# midi-vidi.net
KiCad netlist of a schematic drawn in EAGLE
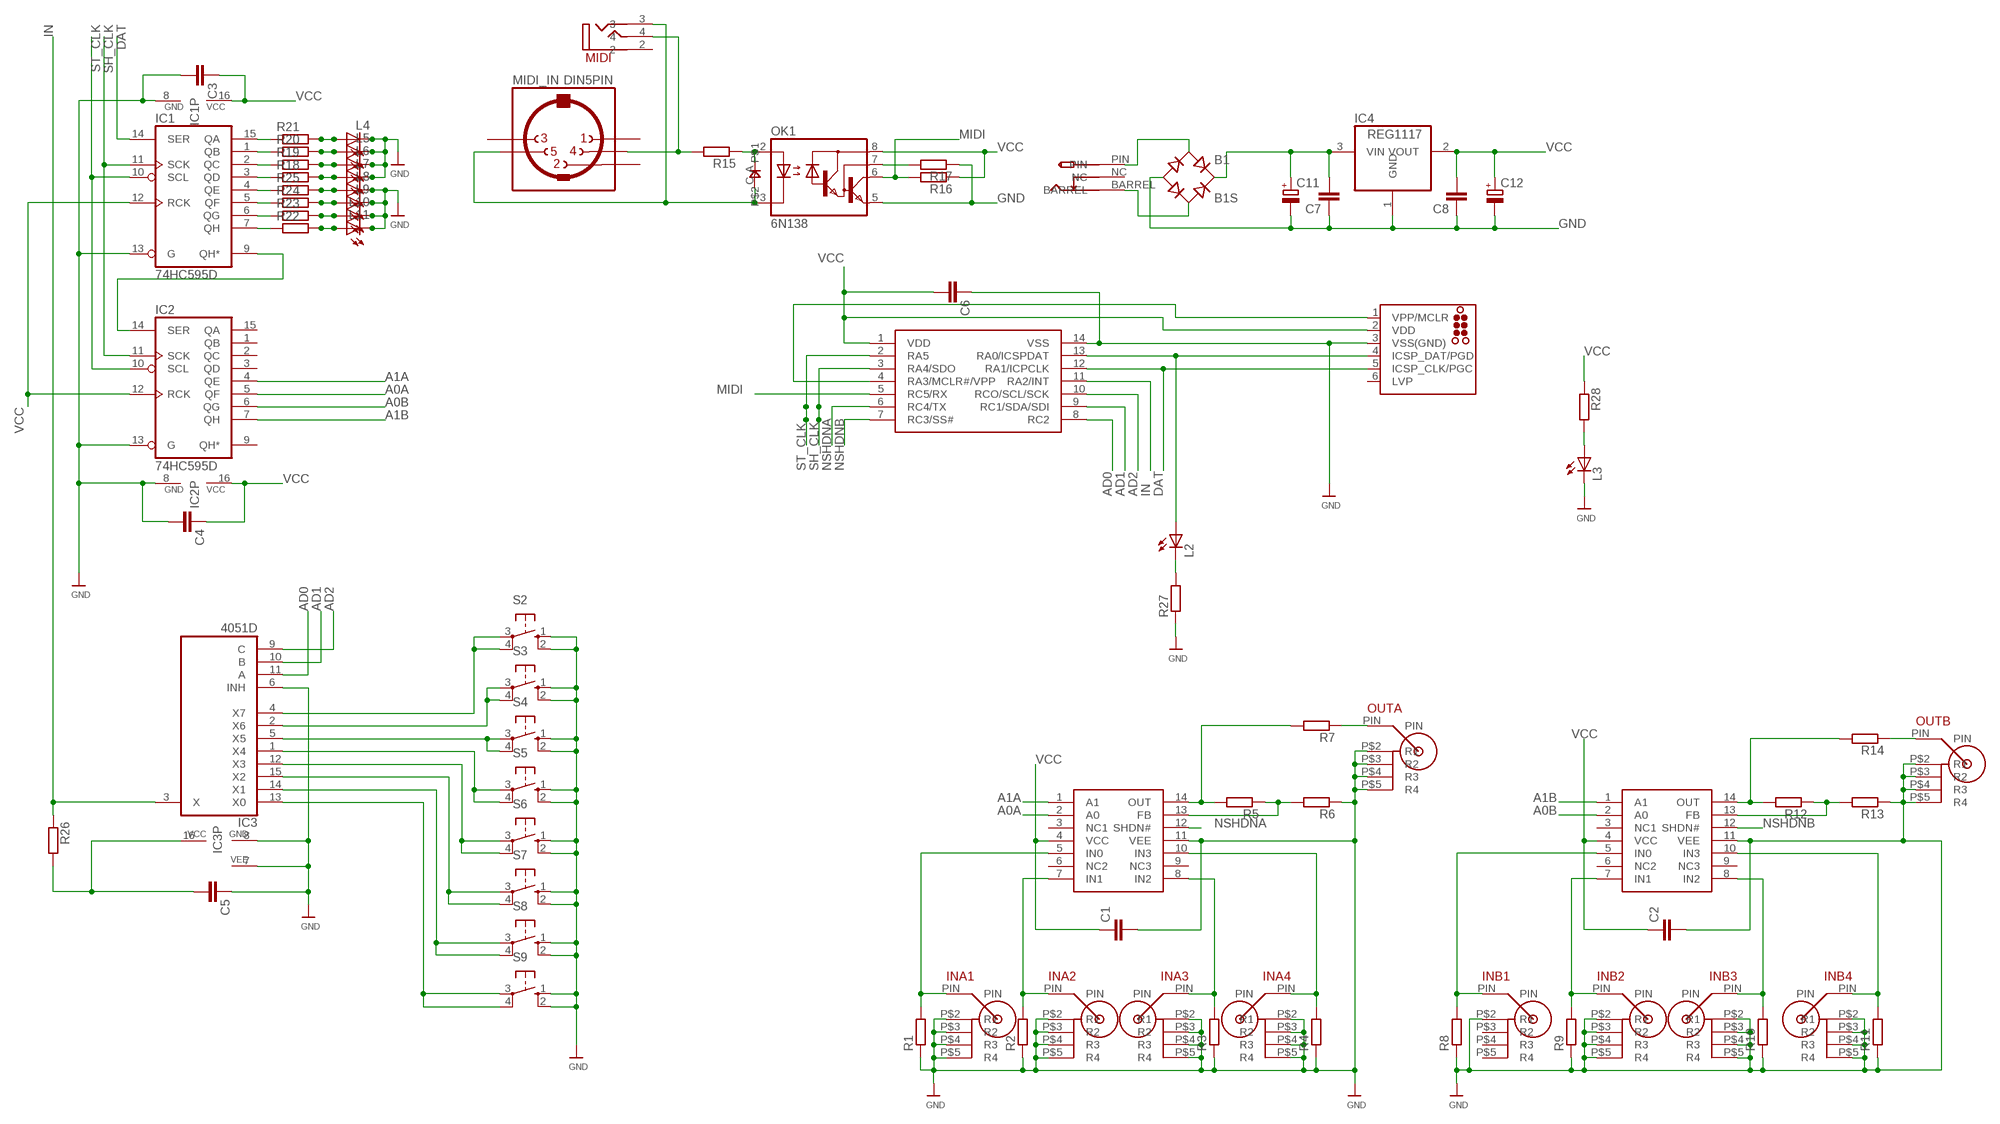
[diagram p0: schematic, sheet 1]

(export (version "E")
  (design (tool "Eeschema 10.0.6"))
  (components
    (comp (ref "B1")
      (value "B1S")
      (footprint "eagle-import:MBS")
      (libsource (lib "eagle-import") (part "BS1"))
    )
    (comp (ref "C1")
      (value "C-EUC0805")
      (footprint "eagle-import:C0805")
      (libsource (lib "eagle-import") (part "C-EUC0805"))
    )
    (comp (ref "C2")
      (value "C-EUC0805")
      (footprint "eagle-import:C0805")
      (libsource (lib "eagle-import") (part "C-EUC0805"))
    )
    (comp (ref "C3")
      (value "C-EUC0805")
      (footprint "eagle-import:C0805")
      (libsource (lib "eagle-import") (part "C-EUC0805"))
    )
    (comp (ref "C4")
      (value "C-EUC0805")
      (footprint "eagle-import:C0805")
      (libsource (lib "eagle-import") (part "C-EUC0805"))
    )
    (comp (ref "C5")
      (value "C-EUC0805")
      (footprint "eagle-import:C0805")
      (libsource (lib "eagle-import") (part "C-EUC0805"))
    )
    (comp (ref "C6")
      (value "C-EUC0805")
      (footprint "eagle-import:C0805")
      (libsource (lib "eagle-import") (part "C-EUC0805"))
    )
    (comp (ref "C7")
      (value "C-EUC0805")
      (footprint "eagle-import:C0805")
      (libsource (lib "eagle-import") (part "C-EUC0805"))
    )
    (comp (ref "C8")
      (value "C-EUC0805")
      (footprint "eagle-import:C0805")
      (libsource (lib "eagle-import") (part "C-EUC0805"))
    )
    (comp (ref "C11")
      (value "CPOL-EUE2,5-6E")
      (footprint "eagle-import:E2,5-6E")
      (libsource (lib "eagle-import") (part "CPOL-EUE2,5-6E"))
    )
    (comp (ref "C12")
      (value "CPOL-EUE2,5-6E")
      (footprint "eagle-import:E2,5-6E")
      (libsource (lib "eagle-import") (part "CPOL-EUE2,5-6E"))
    )
    (comp (ref "IC1")
      (value "74HC595D")
      (footprint "eagle-import:SO16")
      (libsource (lib "eagle-import") (part "74595DHC"))
    )
    (comp (ref "IC2")
      (value "74HC595D")
      (footprint "eagle-import:SO16")
      (libsource (lib "eagle-import") (part "74595DHC"))
    )
    (comp (ref "IC3")
      (value "4051D")
      (footprint "eagle-import:SO16")
      (libsource (lib "eagle-import") (part "4051D"))
    )
    (comp (ref "IC4")
      (value "REG1117")
      (footprint "eagle-import:SOT223")
      (libsource (lib "eagle-import") (part "REG1117"))
    )
    (comp (ref "INA1")
      (value "RCAVERT")
      (footprint "eagle-import:RCAVERT")
      (libsource (lib "eagle-import") (part "RCAVERT"))
    )
    (comp (ref "INA2")
      (value "RCAVERT")
      (footprint "eagle-import:RCAVERT")
      (libsource (lib "eagle-import") (part "RCAVERT"))
    )
    (comp (ref "INA3")
      (value "RCAVERT")
      (footprint "eagle-import:RCAVERT")
      (libsource (lib "eagle-import") (part "RCAVERT"))
    )
    (comp (ref "INA4")
      (value "RCAVERT")
      (footprint "eagle-import:RCAVERT")
      (libsource (lib "eagle-import") (part "RCAVERT"))
    )
    (comp (ref "INB1")
      (value "RCAVERT")
      (footprint "eagle-import:RCAVERT")
      (libsource (lib "eagle-import") (part "RCAVERT"))
    )
    (comp (ref "INB2")
      (value "RCAVERT")
      (footprint "eagle-import:RCAVERT")
      (libsource (lib "eagle-import") (part "RCAVERT"))
    )
    (comp (ref "INB3")
      (value "RCAVERT")
      (footprint "eagle-import:RCAVERT")
      (libsource (lib "eagle-import") (part "RCAVERT"))
    )
    (comp (ref "INB4")
      (value "RCAVERT")
      (footprint "eagle-import:RCAVERT")
      (libsource (lib "eagle-import") (part "RCAVERT"))
    )
    (comp (ref "J1")
      (value "TC2030-MCP-NL")
      (footprint "eagle-import:TC2030-MCP-NL")
      (libsource (lib "eagle-import") (part "TC2030-MCP-NL"))
    )
    (comp (ref "L2")
      (value "LED3MM")
      (footprint "eagle-import:LED3MM")
      (libsource (lib "eagle-import") (part "LED3MM"))
    )
    (comp (ref "L3")
      (value "LED3MM")
      (footprint "eagle-import:LED3MM")
      (libsource (lib "eagle-import") (part "LED3MM"))
    )
    (comp (ref "L4")
      (value "LED3MM")
      (footprint "eagle-import:LED3MM")
      (libsource (lib "eagle-import") (part "LED3MM"))
    )
    (comp (ref "L5")
      (value "LED3MM")
      (footprint "eagle-import:LED3MM")
      (libsource (lib "eagle-import") (part "LED3MM"))
    )
    (comp (ref "L6")
      (value "LED3MM")
      (footprint "eagle-import:LED3MM")
      (libsource (lib "eagle-import") (part "LED3MM"))
    )
    (comp (ref "L7")
      (value "LED3MM")
      (footprint "eagle-import:LED3MM")
      (libsource (lib "eagle-import") (part "LED3MM"))
    )
    (comp (ref "L8")
      (value "LED3MM")
      (footprint "eagle-import:LED3MM")
      (libsource (lib "eagle-import") (part "LED3MM"))
    )
    (comp (ref "L9")
      (value "LED3MM")
      (footprint "eagle-import:LED3MM")
      (libsource (lib "eagle-import") (part "LED3MM"))
    )
    (comp (ref "L10")
      (value "LED3MM")
      (footprint "eagle-import:LED3MM")
      (libsource (lib "eagle-import") (part "LED3MM"))
    )
    (comp (ref "L11")
      (value "LED3MM")
      (footprint "eagle-import:LED3MM")
      (libsource (lib "eagle-import") (part "LED3MM"))
    )
    (comp (ref "MIDI")
      (value "VERTICAL_3_5MM_SOCKET")
      (footprint "eagle-import:VERTICAL_3_5MM_SOCKET")
      (libsource (lib "eagle-import") (part "VERTICAL_3_5MM_SOCKET"))
    )
    (comp (ref "MIDI_IN")
      (value "DIN5PIN")
      (footprint "eagle-import:EDGEDIN")
      (libsource (lib "eagle-import") (part "DIN5PIN"))
    )
    (comp (ref "OK1")
      (value "6N138")
      (footprint "eagle-import:DIL08")
      (fields (field (name "MF") "VISHAY/TELEFUNKEN"))
      (libsource (lib "eagle-import") (part "6N138"))
    )
    (comp (ref "OUTA")
      (value "RCAVERT")
      (footprint "eagle-import:RCAVERT")
      (libsource (lib "eagle-import") (part "RCAVERT"))
    )
    (comp (ref "OUTB")
      (value "RCAVERT")
      (footprint "eagle-import:RCAVERT")
      (libsource (lib "eagle-import") (part "RCAVERT"))
    )
    (comp (ref "R1")
      (value "R-EU_R0805")
      (footprint "eagle-import:R0805")
      (libsource (lib "eagle-import") (part "R-EU_R0805"))
    )
    (comp (ref "R2")
      (value "R-EU_R0805")
      (footprint "eagle-import:R0805")
      (libsource (lib "eagle-import") (part "R-EU_R0805"))
    )
    (comp (ref "R3")
      (value "R-EU_R0805")
      (footprint "eagle-import:R0805")
      (libsource (lib "eagle-import") (part "R-EU_R0805"))
    )
    (comp (ref "R4")
      (value "R-EU_R0805")
      (footprint "eagle-import:R0805")
      (libsource (lib "eagle-import") (part "R-EU_R0805"))
    )
    (comp (ref "R5")
      (value "R-EU_R0805")
      (footprint "eagle-import:R0805")
      (libsource (lib "eagle-import") (part "R-EU_R0805"))
    )
    (comp (ref "R6")
      (value "R-EU_R0805")
      (footprint "eagle-import:R0805")
      (libsource (lib "eagle-import") (part "R-EU_R0805"))
    )
    (comp (ref "R7")
      (value "R-EU_R0805")
      (footprint "eagle-import:R0805")
      (libsource (lib "eagle-import") (part "R-EU_R0805"))
    )
    (comp (ref "R8")
      (value "R-EU_R0805")
      (footprint "eagle-import:R0805")
      (libsource (lib "eagle-import") (part "R-EU_R0805"))
    )
    (comp (ref "R9")
      (value "R-EU_R0805")
      (footprint "eagle-import:R0805")
      (libsource (lib "eagle-import") (part "R-EU_R0805"))
    )
    (comp (ref "R10")
      (value "R-EU_R0805")
      (footprint "eagle-import:R0805")
      (libsource (lib "eagle-import") (part "R-EU_R0805"))
    )
    (comp (ref "R11")
      (value "R-EU_R0805")
      (footprint "eagle-import:R0805")
      (libsource (lib "eagle-import") (part "R-EU_R0805"))
    )
    (comp (ref "R12")
      (value "R-EU_R0805")
      (footprint "eagle-import:R0805")
      (libsource (lib "eagle-import") (part "R-EU_R0805"))
    )
    (comp (ref "R13")
      (value "R-EU_R0805")
      (footprint "eagle-import:R0805")
      (libsource (lib "eagle-import") (part "R-EU_R0805"))
    )
    (comp (ref "R14")
      (value "R-EU_R0805")
      (footprint "eagle-import:R0805")
      (libsource (lib "eagle-import") (part "R-EU_R0805"))
    )
    (comp (ref "R15")
      (value "R-EU_R0805")
      (footprint "eagle-import:R0805")
      (libsource (lib "eagle-import") (part "R-EU_R0805"))
    )
    (comp (ref "R16")
      (value "R-EU_R0805")
      (footprint "eagle-import:R0805")
      (libsource (lib "eagle-import") (part "R-EU_R0805"))
    )
    (comp (ref "R17")
      (value "R-EU_R0805")
      (footprint "eagle-import:R0805")
      (libsource (lib "eagle-import") (part "R-EU_R0805"))
    )
    (comp (ref "R18")
      (value "R-EU_R0805")
      (footprint "eagle-import:R0805")
      (libsource (lib "eagle-import") (part "R-EU_R0805"))
    )
    (comp (ref "R19")
      (value "R-EU_R0805")
      (footprint "eagle-import:R0805")
      (libsource (lib "eagle-import") (part "R-EU_R0805"))
    )
    (comp (ref "R20")
      (value "R-EU_R0805")
      (footprint "eagle-import:R0805")
      (libsource (lib "eagle-import") (part "R-EU_R0805"))
    )
    (comp (ref "R21")
      (value "R-EU_R0805")
      (footprint "eagle-import:R0805")
      (libsource (lib "eagle-import") (part "R-EU_R0805"))
    )
    (comp (ref "R22")
      (value "R-EU_R0805")
      (footprint "eagle-import:R0805")
      (libsource (lib "eagle-import") (part "R-EU_R0805"))
    )
    (comp (ref "R23")
      (value "R-EU_R0805")
      (footprint "eagle-import:R0805")
      (libsource (lib "eagle-import") (part "R-EU_R0805"))
    )
    (comp (ref "R24")
      (value "R-EU_R0805")
      (footprint "eagle-import:R0805")
      (libsource (lib "eagle-import") (part "R-EU_R0805"))
    )
    (comp (ref "R25")
      (value "R-EU_R0805")
      (footprint "eagle-import:R0805")
      (libsource (lib "eagle-import") (part "R-EU_R0805"))
    )
    (comp (ref "R26")
      (value "R-EU_R0805")
      (footprint "eagle-import:R0805")
      (libsource (lib "eagle-import") (part "R-EU_R0805"))
    )
    (comp (ref "R27")
      (value "R-EU_R0805")
      (footprint "eagle-import:R0805")
      (libsource (lib "eagle-import") (part "R-EU_R0805"))
    )
    (comp (ref "R28")
      (value "R-EU_R0805")
      (footprint "eagle-import:R0805")
      (libsource (lib "eagle-import") (part "R-EU_R0805"))
    )
    (comp (ref "S2")
      (value "10-XX")
      (footprint "eagle-import:B3F-10XX")
      (fields (field (name "MPN") "B3F-1000"))
      (libsource (lib "eagle-import") (part "10-XX"))
    )
    (comp (ref "S3")
      (value "10-XX")
      (footprint "eagle-import:B3F-10XX")
      (fields (field (name "MPN") "B3F-1000"))
      (libsource (lib "eagle-import") (part "10-XX"))
    )
    (comp (ref "S4")
      (value "10-XX")
      (footprint "eagle-import:B3F-10XX")
      (fields (field (name "MPN") "B3F-1000"))
      (libsource (lib "eagle-import") (part "10-XX"))
    )
    (comp (ref "S5")
      (value "10-XX")
      (footprint "eagle-import:B3F-10XX")
      (fields (field (name "MPN") "B3F-1000"))
      (libsource (lib "eagle-import") (part "10-XX"))
    )
    (comp (ref "S6")
      (value "10-XX")
      (footprint "eagle-import:B3F-10XX")
      (fields (field (name "MPN") "B3F-1000"))
      (libsource (lib "eagle-import") (part "10-XX"))
    )
    (comp (ref "S7")
      (value "10-XX")
      (footprint "eagle-import:B3F-10XX")
      (fields (field (name "MPN") "B3F-1000"))
      (libsource (lib "eagle-import") (part "10-XX"))
    )
    (comp (ref "S8")
      (value "10-XX")
      (footprint "eagle-import:B3F-10XX")
      (fields (field (name "MPN") "B3F-1000"))
      (libsource (lib "eagle-import") (part "10-XX"))
    )
    (comp (ref "S9")
      (value "10-XX")
      (footprint "eagle-import:B3F-10XX")
      (fields (field (name "MPN") "B3F-1000"))
      (libsource (lib "eagle-import") (part "10-XX"))
    )
    (comp (ref "U$2")
      (value "PWR_SOCKET_2_1MM")
      (footprint "eagle-import:PWR_SOCKET_2_1MM")
      (libsource (lib "eagle-import") (part "PWR_SOCKET_2_1MM"))
    )
    (comp (ref "U$5")
      (value "0805DIODE")
      (footprint "eagle-import:0805DIODE")
      (libsource (lib "eagle-import") (part "0805DIODE"))
    )
    (comp (ref "U$12")
      (value "MAX4311SO14")
      (footprint "eagle-import:SO14")
      (libsource (lib "eagle-import") (part "MAX4311SO14"))
    )
    (comp (ref "U$13")
      (value "MAX4311SO14")
      (footprint "eagle-import:SO14")
      (libsource (lib "eagle-import") (part "MAX4311SO14"))
    )
    (comp (ref "U$14")
      (value "PIC16F1825SO14")
      (footprint "eagle-import:SO14")
      (libsource (lib "eagle-import") (part "PIC16F1825SO14"))
    )
  )
  (nets
    (net (code "1") (name "/A0A") (class "Default")
      (node (ref "IC2") (pin "5") (pinfunction "QF_5") (pintype "tri_state"))
      (node (ref "U$13") (pin "2") (pinfunction "A0_2") (pintype "bidirectional"))
    )
    (net (code "2") (name "/A0B") (class "Default")
      (node (ref "IC2") (pin "6") (pinfunction "QG_6") (pintype "tri_state"))
      (node (ref "U$12") (pin "2") (pinfunction "A0_2") (pintype "bidirectional"))
    )
    (net (code "3") (name "/A1A") (class "Default")
      (node (ref "IC2") (pin "4") (pinfunction "QE_4") (pintype "tri_state"))
      (node (ref "U$13") (pin "1") (pinfunction "A1_1") (pintype "bidirectional"))
    )
    (net (code "4") (name "/A1B") (class "Default")
      (node (ref "IC2") (pin "7") (pinfunction "QH_7") (pintype "tri_state"))
      (node (ref "U$12") (pin "1") (pinfunction "A1_1") (pintype "bidirectional"))
    )
    (net (code "5") (name "/AD0") (class "Default")
      (node (ref "IC3") (pin "11") (pinfunction "A_11") (pintype "input"))
      (node (ref "U$14") (pin "8") (pinfunction "RC2_8") (pintype "bidirectional"))
    )
    (net (code "6") (name "/AD1") (class "Default")
      (node (ref "IC3") (pin "10") (pinfunction "B_10") (pintype "input"))
      (node (ref "U$14") (pin "9") (pinfunction "RC1/SDA/SDI_9") (pintype "bidirectional"))
    )
    (net (code "7") (name "/AD2") (class "Default")
      (node (ref "IC3") (pin "9") (pinfunction "C_9") (pintype "input"))
      (node (ref "U$14") (pin "10") (pinfunction "RCO/SCL/SCK_10") (pintype "bidirectional"))
    )
    (net (code "8") (name "/DAT") (class "Default")
      (node (ref "IC1") (pin "14") (pinfunction "SER_14") (pintype "input"))
      (node (ref "J1") (pin "5") (pinfunction "ICSP_CLK/PGC_5") (pintype "output"))
      (node (ref "U$14") (pin "12") (pinfunction "RA1/ICPCLK_12") (pintype "bidirectional"))
    )
    (net (code "9") (name "/IN") (class "Default")
      (node (ref "IC3") (pin "3") (pinfunction "X_3") (pintype "bidirectional"))
      (node (ref "R26") (pin "1") (pinfunction "1_1") (pintype "passive"))
      (node (ref "U$14") (pin "11") (pinfunction "RA2/INT_11") (pintype "bidirectional"))
    )
    (net (code "10") (name "/MIDI") (class "Default")
      (node (ref "OK1") (pin "6") (pinfunction "VO_6") (pintype "passive"))
      (node (ref "R16") (pin "2") (pinfunction "2_2") (pintype "passive"))
      (node (ref "U$14") (pin "5") (pinfunction "RC5/RX_5") (pintype "bidirectional"))
    )
    (net (code "11") (name "/NSHDNA") (class "Default")
      (node (ref "U$13") (pin "12") (pinfunction "SHDN#_12") (pintype "bidirectional"))
      (node (ref "U$14") (pin "6") (pinfunction "RC4/TX_6") (pintype "bidirectional"))
    )
    (net (code "12") (name "/NSHDNB") (class "Default")
      (node (ref "U$12") (pin "12") (pinfunction "SHDN#_12") (pintype "bidirectional"))
      (node (ref "U$14") (pin "7") (pinfunction "RC3/SS#_7") (pintype "bidirectional"))
    )
    (net (code "13") (name "/SH_CLK") (class "Default")
      (node (ref "IC1") (pin "11") (pinfunction "SCK_11") (pintype "input"))
      (node (ref "IC2") (pin "11") (pinfunction "SCK_11") (pintype "input"))
      (node (ref "U$14") (pin "3") (pinfunction "RA4/SDO_3") (pintype "bidirectional"))
    )
    (net (code "14") (name "/ST_CLK") (class "Default")
      (node (ref "IC1") (pin "10") (pinfunction "SCL_10") (pintype "input"))
      (node (ref "IC2") (pin "10") (pinfunction "SCL_10") (pintype "input"))
      (node (ref "U$14") (pin "2") (pinfunction "RA5_2") (pintype "bidirectional"))
    )
    (net (code "15") (name "/VCC") (class "Default")
      (node (ref "C1") (pin "1") (pinfunction "1_1") (pintype "passive"))
      (node (ref "C12") (pin "+") (pinfunction "+_+") (pintype "passive"))
      (node (ref "C2") (pin "1") (pinfunction "1_1") (pintype "passive"))
      (node (ref "C3") (pin "1") (pinfunction "1_1") (pintype "passive"))
      (node (ref "C4") (pin "1") (pinfunction "1_1") (pintype "passive"))
      (node (ref "C5") (pin "2") (pinfunction "2_2") (pintype "passive"))
      (node (ref "C6") (pin "2") (pinfunction "2_2") (pintype "passive"))
      (node (ref "C8") (pin "2") (pinfunction "2_2") (pintype "passive"))
      (node (ref "IC1") (pin "12") (pinfunction "RCK_12") (pintype "input"))
      (node (ref "IC1") (pin "16") (pinfunction "VCC_16") (pintype "power_in"))
      (node (ref "IC2") (pin "12") (pinfunction "RCK_12") (pintype "input"))
      (node (ref "IC2") (pin "16") (pinfunction "VCC_16") (pintype "power_in"))
      (node (ref "IC3") (pin "16") (pinfunction "VCC_16") (pintype "power_in"))
      (node (ref "IC4") (pin "2") (pinfunction "VOUT_2") (pintype "output"))
      (node (ref "J1") (pin "2") (pinfunction "VDD_2") (pintype "power_in"))
      (node (ref "OK1") (pin "8") (pinfunction "VCC_8") (pintype "passive"))
      (node (ref "R16") (pin "1") (pinfunction "1_1") (pintype "passive"))
      (node (ref "R26") (pin "2") (pinfunction "2_2") (pintype "passive"))
      (node (ref "R28") (pin "1") (pinfunction "1_1") (pintype "passive"))
      (node (ref "U$12") (pin "4") (pinfunction "VCC_4") (pintype "bidirectional"))
      (node (ref "U$13") (pin "4") (pinfunction "VCC_4") (pintype "bidirectional"))
      (node (ref "U$14") (pin "1") (pinfunction "VDD_1") (pintype "power_in"))
    )
    (net (code "16") (name "GND") (class "Default")
      (node (ref "B1") (pin "-") (pinfunction "-_-") (pintype "passive"))
      (node (ref "C1") (pin "2") (pinfunction "2_2") (pintype "passive"))
      (node (ref "C11") (pin "-") (pinfunction "-_-") (pintype "passive"))
      (node (ref "C12") (pin "-") (pinfunction "-_-") (pintype "passive"))
      (node (ref "C2") (pin "2") (pinfunction "2_2") (pintype "passive"))
      (node (ref "C3") (pin "2") (pinfunction "2_2") (pintype "passive"))
      (node (ref "C4") (pin "2") (pinfunction "2_2") (pintype "passive"))
      (node (ref "C5") (pin "1") (pinfunction "1_1") (pintype "passive"))
      (node (ref "C6") (pin "1") (pinfunction "1_1") (pintype "passive"))
      (node (ref "C7") (pin "1") (pinfunction "1_1") (pintype "passive"))
      (node (ref "C8") (pin "1") (pinfunction "1_1") (pintype "passive"))
      (node (ref "IC1") (pin "13") (pinfunction "G_13") (pintype "input"))
      (node (ref "IC1") (pin "8") (pinfunction "GND_8") (pintype "power_in"))
      (node (ref "IC2") (pin "13") (pinfunction "G_13") (pintype "input"))
      (node (ref "IC2") (pin "8") (pinfunction "GND_8") (pintype "power_in"))
      (node (ref "IC3") (pin "6") (pinfunction "INH_6") (pintype "input"))
      (node (ref "IC3") (pin "7") (pinfunction "VEE_7") (pintype "power_in"))
      (node (ref "IC3") (pin "8") (pinfunction "GND_8") (pintype "power_in"))
      (node (ref "IC4") (pin "1") (pinfunction "GND_1") (pintype "power_in"))
      (node (ref "INA1") (pin "P$2") (pinfunction "R1_P$2") (pintype "bidirectional"))
      (node (ref "INA1") (pin "P$3") (pinfunction "R2_P$3") (pintype "bidirectional"))
      (node (ref "INA1") (pin "P$4") (pinfunction "R3_P$4") (pintype "bidirectional"))
      (node (ref "INA1") (pin "P$5") (pinfunction "R4_P$5") (pintype "bidirectional"))
      (node (ref "INA2") (pin "P$2") (pinfunction "R1_P$2") (pintype "bidirectional"))
      (node (ref "INA2") (pin "P$3") (pinfunction "R2_P$3") (pintype "bidirectional"))
      (node (ref "INA2") (pin "P$4") (pinfunction "R3_P$4") (pintype "bidirectional"))
      (node (ref "INA2") (pin "P$5") (pinfunction "R4_P$5") (pintype "bidirectional"))
      (node (ref "INA3") (pin "P$2") (pinfunction "R1_P$2") (pintype "bidirectional"))
      (node (ref "INA3") (pin "P$3") (pinfunction "R2_P$3") (pintype "bidirectional"))
      (node (ref "INA3") (pin "P$4") (pinfunction "R3_P$4") (pintype "bidirectional"))
      (node (ref "INA3") (pin "P$5") (pinfunction "R4_P$5") (pintype "bidirectional"))
      (node (ref "INA4") (pin "P$2") (pinfunction "R1_P$2") (pintype "bidirectional"))
      (node (ref "INA4") (pin "P$3") (pinfunction "R2_P$3") (pintype "bidirectional"))
      (node (ref "INA4") (pin "P$4") (pinfunction "R3_P$4") (pintype "bidirectional"))
      (node (ref "INA4") (pin "P$5") (pinfunction "R4_P$5") (pintype "bidirectional"))
      (node (ref "INB1") (pin "P$2") (pinfunction "R1_P$2") (pintype "bidirectional"))
      (node (ref "INB2") (pin "P$2") (pinfunction "R1_P$2") (pintype "bidirectional"))
      (node (ref "INB2") (pin "P$3") (pinfunction "R2_P$3") (pintype "bidirectional"))
      (node (ref "INB2") (pin "P$4") (pinfunction "R3_P$4") (pintype "bidirectional"))
      (node (ref "INB2") (pin "P$5") (pinfunction "R4_P$5") (pintype "bidirectional"))
      (node (ref "INB3") (pin "P$2") (pinfunction "R1_P$2") (pintype "bidirectional"))
      (node (ref "INB3") (pin "P$3") (pinfunction "R2_P$3") (pintype "bidirectional"))
      (node (ref "INB3") (pin "P$4") (pinfunction "R3_P$4") (pintype "bidirectional"))
      (node (ref "INB3") (pin "P$5") (pinfunction "R4_P$5") (pintype "bidirectional"))
      (node (ref "INB4") (pin "P$2") (pinfunction "R1_P$2") (pintype "bidirectional"))
      (node (ref "INB4") (pin "P$3") (pinfunction "R2_P$3") (pintype "bidirectional"))
      (node (ref "INB4") (pin "P$4") (pinfunction "R3_P$4") (pintype "bidirectional"))
      (node (ref "INB4") (pin "P$5") (pinfunction "R4_P$5") (pintype "bidirectional"))
      (node (ref "J1") (pin "3") (pinfunction "VSS(GND)_3") (pintype "power_in"))
      (node (ref "L10") (pin "K") (pinfunction "C_K") (pintype "passive"))
      (node (ref "L11") (pin "K") (pinfunction "C_K") (pintype "passive"))
      (node (ref "L3") (pin "K") (pinfunction "C_K") (pintype "passive"))
      (node (ref "L4") (pin "K") (pinfunction "C_K") (pintype "passive"))
      (node (ref "L5") (pin "K") (pinfunction "C_K") (pintype "passive"))
      (node (ref "L6") (pin "K") (pinfunction "C_K") (pintype "passive"))
      (node (ref "L7") (pin "K") (pinfunction "C_K") (pintype "passive"))
      (node (ref "L8") (pin "K") (pinfunction "C_K") (pintype "passive"))
      (node (ref "L9") (pin "K") (pinfunction "C_K") (pintype "passive"))
      (node (ref "OK1") (pin "5") (pinfunction "GND_5") (pintype "passive"))
      (node (ref "OUTA") (pin "P$2") (pinfunction "R1_P$2") (pintype "bidirectional"))
      (node (ref "OUTA") (pin "P$3") (pinfunction "R2_P$3") (pintype "bidirectional"))
      (node (ref "OUTA") (pin "P$4") (pinfunction "R3_P$4") (pintype "bidirectional"))
      (node (ref "OUTA") (pin "P$5") (pinfunction "R4_P$5") (pintype "bidirectional"))
      (node (ref "OUTB") (pin "P$2") (pinfunction "R1_P$2") (pintype "bidirectional"))
      (node (ref "OUTB") (pin "P$3") (pinfunction "R2_P$3") (pintype "bidirectional"))
      (node (ref "OUTB") (pin "P$4") (pinfunction "R3_P$4") (pintype "bidirectional"))
      (node (ref "OUTB") (pin "P$5") (pinfunction "R4_P$5") (pintype "bidirectional"))
      (node (ref "R1") (pin "1") (pinfunction "1_1") (pintype "passive"))
      (node (ref "R10") (pin "1") (pinfunction "1_1") (pintype "passive"))
      (node (ref "R11") (pin "1") (pinfunction "1_1") (pintype "passive"))
      (node (ref "R13") (pin "1") (pinfunction "1_1") (pintype "passive"))
      (node (ref "R17") (pin "1") (pinfunction "1_1") (pintype "passive"))
      (node (ref "R2") (pin "1") (pinfunction "1_1") (pintype "passive"))
      (node (ref "R27") (pin "1") (pinfunction "1_1") (pintype "passive"))
      (node (ref "R3") (pin "1") (pinfunction "1_1") (pintype "passive"))
      (node (ref "R4") (pin "1") (pinfunction "1_1") (pintype "passive"))
      (node (ref "R6") (pin "1") (pinfunction "1_1") (pintype "passive"))
      (node (ref "R8") (pin "1") (pinfunction "1_1") (pintype "passive"))
      (node (ref "R9") (pin "1") (pinfunction "1_1") (pintype "passive"))
      (node (ref "S2") (pin "1") (pinfunction "S_1") (pintype "passive"))
      (node (ref "S2") (pin "2") (pinfunction "S1_2") (pintype "passive"))
      (node (ref "S3") (pin "1") (pinfunction "S_1") (pintype "passive"))
      (node (ref "S3") (pin "2") (pinfunction "S1_2") (pintype "passive"))
      (node (ref "S4") (pin "1") (pinfunction "S_1") (pintype "passive"))
      (node (ref "S4") (pin "2") (pinfunction "S1_2") (pintype "passive"))
      (node (ref "S5") (pin "1") (pinfunction "S_1") (pintype "passive"))
      (node (ref "S5") (pin "2") (pinfunction "S1_2") (pintype "passive"))
      (node (ref "S6") (pin "1") (pinfunction "S_1") (pintype "passive"))
      (node (ref "S6") (pin "2") (pinfunction "S1_2") (pintype "passive"))
      (node (ref "S7") (pin "1") (pinfunction "S_1") (pintype "passive"))
      (node (ref "S7") (pin "2") (pinfunction "S1_2") (pintype "passive"))
      (node (ref "S8") (pin "1") (pinfunction "S_1") (pintype "passive"))
      (node (ref "S8") (pin "2") (pinfunction "S1_2") (pintype "passive"))
      (node (ref "S9") (pin "1") (pinfunction "S_1") (pintype "passive"))
      (node (ref "S9") (pin "2") (pinfunction "S1_2") (pintype "passive"))
      (node (ref "U$12") (pin "11") (pinfunction "VEE_11") (pintype "bidirectional"))
      (node (ref "U$13") (pin "11") (pinfunction "VEE_11") (pintype "bidirectional"))
      (node (ref "U$14") (pin "14") (pinfunction "VSS_14") (pintype "power_in"))
    )
    (net (code "17") (name "Net-(B1-PadAC1)") (class "Default")
      (node (ref "B1") (pin "AC1") (pinfunction "AC1_AC1") (pintype "passive"))
      (node (ref "U$2") (pin "PIN") (pinfunction "PIN_PIN") (pintype "bidirectional"))
    )
    (net (code "18") (name "Net-(B1-PadAC2)") (class "Default")
      (node (ref "B1") (pin "AC2") (pinfunction "AC2_AC2") (pintype "passive"))
      (node (ref "U$2") (pin "BARREL") (pinfunction "BARREL_BARREL") (pintype "bidirectional"))
    )
    (net (code "19") (name "Net-(IC1A-QA)") (class "Default")
      (node (ref "IC1") (pin "15") (pinfunction "QA_15") (pintype "tri_state"))
      (node (ref "R21") (pin "1") (pinfunction "1_1") (pintype "passive"))
    )
    (net (code "20") (name "Net-(IC1A-QB)") (class "Default")
      (node (ref "IC1") (pin "1") (pinfunction "QB_1") (pintype "tri_state"))
      (node (ref "R20") (pin "1") (pinfunction "1_1") (pintype "passive"))
    )
    (net (code "21") (name "Net-(IC1A-QC)") (class "Default")
      (node (ref "IC1") (pin "2") (pinfunction "QC_2") (pintype "tri_state"))
      (node (ref "R19") (pin "1") (pinfunction "1_1") (pintype "passive"))
    )
    (net (code "22") (name "Net-(IC1A-QD)") (class "Default")
      (node (ref "IC1") (pin "3") (pinfunction "QD_3") (pintype "tri_state"))
      (node (ref "R18") (pin "1") (pinfunction "1_1") (pintype "passive"))
    )
    (net (code "23") (name "Net-(IC1A-QE)") (class "Default")
      (node (ref "IC1") (pin "4") (pinfunction "QE_4") (pintype "tri_state"))
      (node (ref "R25") (pin "1") (pinfunction "1_1") (pintype "passive"))
    )
    (net (code "24") (name "Net-(IC1A-QF)") (class "Default")
      (node (ref "IC1") (pin "5") (pinfunction "QF_5") (pintype "tri_state"))
      (node (ref "R24") (pin "1") (pinfunction "1_1") (pintype "passive"))
    )
    (net (code "25") (name "Net-(IC1A-QG)") (class "Default")
      (node (ref "IC1") (pin "6") (pinfunction "QG_6") (pintype "tri_state"))
      (node (ref "R23") (pin "1") (pinfunction "1_1") (pintype "passive"))
    )
    (net (code "26") (name "Net-(IC1A-QH)") (class "Default")
      (node (ref "IC1") (pin "7") (pinfunction "QH_7") (pintype "tri_state"))
      (node (ref "R22") (pin "1") (pinfunction "1_1") (pintype "passive"))
    )
    (net (code "27") (name "Net-(IC1A-QH*)") (class "Default")
      (node (ref "IC1") (pin "9") (pinfunction "QH*_9") (pintype "tri_state"))
      (node (ref "IC2") (pin "14") (pinfunction "SER_14") (pintype "input"))
    )
    (net (code "28") (name "Net-(IC3A-X0)") (class "Default")
      (node (ref "IC3") (pin "13") (pinfunction "X0_13") (pintype "bidirectional"))
      (node (ref "S9") (pin "3") (pinfunction "P_3") (pintype "passive"))
      (node (ref "S9") (pin "4") (pinfunction "P1_4") (pintype "passive"))
    )
    (net (code "29") (name "Net-(IC3A-X1)") (class "Default")
      (node (ref "IC3") (pin "14") (pinfunction "X1_14") (pintype "bidirectional"))
      (node (ref "S8") (pin "3") (pinfunction "P_3") (pintype "passive"))
      (node (ref "S8") (pin "4") (pinfunction "P1_4") (pintype "passive"))
    )
    (net (code "30") (name "Net-(IC3A-X2)") (class "Default")
      (node (ref "IC3") (pin "15") (pinfunction "X2_15") (pintype "bidirectional"))
      (node (ref "S7") (pin "3") (pinfunction "P_3") (pintype "passive"))
      (node (ref "S7") (pin "4") (pinfunction "P1_4") (pintype "passive"))
    )
    (net (code "31") (name "Net-(IC3A-X3)") (class "Default")
      (node (ref "IC3") (pin "12") (pinfunction "X3_12") (pintype "bidirectional"))
      (node (ref "S6") (pin "3") (pinfunction "P_3") (pintype "passive"))
      (node (ref "S6") (pin "4") (pinfunction "P1_4") (pintype "passive"))
    )
    (net (code "32") (name "Net-(IC3A-X4)") (class "Default")
      (node (ref "IC3") (pin "1") (pinfunction "X4_1") (pintype "bidirectional"))
      (node (ref "S5") (pin "3") (pinfunction "P_3") (pintype "passive"))
      (node (ref "S5") (pin "4") (pinfunction "P1_4") (pintype "passive"))
    )
    (net (code "33") (name "Net-(IC3A-X5)") (class "Default")
      (node (ref "IC3") (pin "5") (pinfunction "X5_5") (pintype "bidirectional"))
      (node (ref "S4") (pin "3") (pinfunction "P_3") (pintype "passive"))
      (node (ref "S4") (pin "4") (pinfunction "P1_4") (pintype "passive"))
    )
    (net (code "34") (name "Net-(IC3A-X6)") (class "Default")
      (node (ref "IC3") (pin "2") (pinfunction "X6_2") (pintype "bidirectional"))
      (node (ref "S3") (pin "3") (pinfunction "P_3") (pintype "passive"))
      (node (ref "S3") (pin "4") (pinfunction "P1_4") (pintype "passive"))
    )
    (net (code "35") (name "Net-(IC3A-X7)") (class "Default")
      (node (ref "IC3") (pin "4") (pinfunction "X7_4") (pintype "bidirectional"))
      (node (ref "S2") (pin "3") (pinfunction "P_3") (pintype "passive"))
      (node (ref "S2") (pin "4") (pinfunction "P1_4") (pintype "passive"))
    )
    (net (code "36") (name "Net-(IC4-VIN)") (class "Default")
      (node (ref "B1") (pin "+") (pinfunction "+_+") (pintype "passive"))
      (node (ref "C11") (pin "+") (pinfunction "+_+") (pintype "passive"))
      (node (ref "C7") (pin "2") (pinfunction "2_2") (pintype "passive"))
      (node (ref "IC4") (pin "3") (pinfunction "VIN_3") (pintype "input"))
    )
    (net (code "37") (name "Net-(J1-ICSP_DAT{slash}PGD)") (class "Default")
      (node (ref "J1") (pin "4") (pinfunction "ICSP_DAT/PGD_4") (pintype "bidirectional"))
      (node (ref "L2") (pin "A") (pinfunction "A_A") (pintype "passive"))
      (node (ref "U$14") (pin "13") (pinfunction "RA0/ICSPDAT_13") (pintype "bidirectional"))
    )
    (net (code "38") (name "Net-(J1-VPP{slash}MCLR)") (class "Default")
      (node (ref "J1") (pin "1") (pinfunction "VPP/MCLR_1") (pintype "passive"))
      (node (ref "U$14") (pin "4") (pinfunction "RA3/MCLR#/VPP_4") (pintype "input"))
    )
    (net (code "39") (name "Net-(L2-C)") (class "Default")
      (node (ref "L2") (pin "K") (pinfunction "C_K") (pintype "passive"))
      (node (ref "R27") (pin "2") (pinfunction "2_2") (pintype "passive"))
    )
    (net (code "40") (name "Net-(L3-PadA)") (class "Default")
      (node (ref "L3") (pin "A") (pinfunction "A_A") (pintype "passive"))
      (node (ref "R28") (pin "2") (pinfunction "2_2") (pintype "passive"))
    )
    (net (code "41") (name "Net-(L4-PadA)") (class "Default")
      (node (ref "L4") (pin "A") (pinfunction "A_A") (pintype "passive"))
      (node (ref "R21") (pin "2") (pinfunction "2_2") (pintype "passive"))
    )
    (net (code "42") (name "Net-(L5-PadA)") (class "Default")
      (node (ref "L5") (pin "A") (pinfunction "A_A") (pintype "passive"))
      (node (ref "R20") (pin "2") (pinfunction "2_2") (pintype "passive"))
    )
    (net (code "43") (name "Net-(L6-PadA)") (class "Default")
      (node (ref "L6") (pin "A") (pinfunction "A_A") (pintype "passive"))
      (node (ref "R19") (pin "2") (pinfunction "2_2") (pintype "passive"))
    )
    (net (code "44") (name "Net-(L7-PadA)") (class "Default")
      (node (ref "L7") (pin "A") (pinfunction "A_A") (pintype "passive"))
      (node (ref "R18") (pin "2") (pinfunction "2_2") (pintype "passive"))
    )
    (net (code "45") (name "Net-(L8-PadA)") (class "Default")
      (node (ref "L8") (pin "A") (pinfunction "A_A") (pintype "passive"))
      (node (ref "R25") (pin "2") (pinfunction "2_2") (pintype "passive"))
    )
    (net (code "46") (name "Net-(L9-PadA)") (class "Default")
      (node (ref "L9") (pin "A") (pinfunction "A_A") (pintype "passive"))
      (node (ref "R24") (pin "2") (pinfunction "2_2") (pintype "passive"))
    )
    (net (code "47") (name "Net-(L10-PadA)") (class "Default")
      (node (ref "L10") (pin "A") (pinfunction "A_A") (pintype "passive"))
      (node (ref "R23") (pin "2") (pinfunction "2_2") (pintype "passive"))
    )
    (net (code "48") (name "Net-(L11-PadA)") (class "Default")
      (node (ref "L11") (pin "A") (pinfunction "A_A") (pintype "passive"))
      (node (ref "R22") (pin "2") (pinfunction "2_2") (pintype "passive"))
    )
    (net (code "49") (name "Net-(MIDI-Pad4)") (class "Default")
      (node (ref "MIDI") (pin "4") (pinfunction "4_4") (pintype "bidirectional"))
      (node (ref "MIDI_IN") (pin "4") (pinfunction "4_4") (pintype "passive"))
      (node (ref "R15") (pin "2") (pinfunction "2_2") (pintype "passive"))
    )
    (net (code "50") (name "Net-(OK1-A)") (class "Default")
      (node (ref "OK1") (pin "2") (pinfunction "A_2") (pintype "passive"))
      (node (ref "R15") (pin "1") (pinfunction "1_1") (pintype "passive"))
      (node (ref "U$5") (pin "A") (pinfunction "P$2_A") (pintype "bidirectional"))
    )
    (net (code "51") (name "Net-(OK1-C)") (class "Default")
      (node (ref "MIDI") (pin "3") (pinfunction "3_3") (pintype "bidirectional"))
      (node (ref "MIDI_IN") (pin "5") (pinfunction "5_5") (pintype "passive"))
      (node (ref "OK1") (pin "3") (pinfunction "C_3") (pintype "passive"))
      (node (ref "U$5") (pin "C") (pinfunction "P$1_C") (pintype "bidirectional"))
    )
    (net (code "52") (name "Net-(OK1-VB)") (class "Default")
      (node (ref "OK1") (pin "7") (pinfunction "VB_7") (pintype "passive"))
      (node (ref "R17") (pin "2") (pinfunction "2_2") (pintype "passive"))
    )
    (net (code "53") (name "Net-(OUTA-PadPIN)") (class "Default")
      (node (ref "OUTA") (pin "PIN") (pinfunction "PIN_PIN") (pintype "bidirectional"))
      (node (ref "R7") (pin "1") (pinfunction "1_1") (pintype "passive"))
    )
    (net (code "54") (name "Net-(OUTB-PadPIN)") (class "Default")
      (node (ref "OUTB") (pin "PIN") (pinfunction "PIN_PIN") (pintype "bidirectional"))
      (node (ref "R14") (pin "1") (pinfunction "1_1") (pintype "passive"))
    )
    (net (code "55") (name "Net-(U$12-FB)") (class "Default")
      (node (ref "R12") (pin "1") (pinfunction "1_1") (pintype "passive"))
      (node (ref "R13") (pin "2") (pinfunction "2_2") (pintype "passive"))
      (node (ref "U$12") (pin "13") (pinfunction "FB_13") (pintype "bidirectional"))
    )
    (net (code "56") (name "Net-(U$12-IN0)") (class "Default")
      (node (ref "INB1") (pin "PIN") (pinfunction "PIN_PIN") (pintype "bidirectional"))
      (node (ref "R8") (pin "2") (pinfunction "2_2") (pintype "passive"))
      (node (ref "U$12") (pin "5") (pinfunction "IN0_5") (pintype "bidirectional"))
    )
    (net (code "57") (name "Net-(U$12-IN1)") (class "Default")
      (node (ref "INB2") (pin "PIN") (pinfunction "PIN_PIN") (pintype "bidirectional"))
      (node (ref "R9") (pin "2") (pinfunction "2_2") (pintype "passive"))
      (node (ref "U$12") (pin "7") (pinfunction "IN1_7") (pintype "bidirectional"))
    )
    (net (code "58") (name "Net-(U$12-IN2)") (class "Default")
      (node (ref "INB3") (pin "PIN") (pinfunction "PIN_PIN") (pintype "bidirectional"))
      (node (ref "R10") (pin "2") (pinfunction "2_2") (pintype "passive"))
      (node (ref "U$12") (pin "8") (pinfunction "IN2_8") (pintype "bidirectional"))
    )
    (net (code "59") (name "Net-(U$12-IN3)") (class "Default")
      (node (ref "INB4") (pin "PIN") (pinfunction "PIN_PIN") (pintype "bidirectional"))
      (node (ref "R11") (pin "2") (pinfunction "2_2") (pintype "passive"))
      (node (ref "U$12") (pin "10") (pinfunction "IN3_10") (pintype "bidirectional"))
    )
    (net (code "60") (name "Net-(U$12-OUT)") (class "Default")
      (node (ref "R12") (pin "2") (pinfunction "2_2") (pintype "passive"))
      (node (ref "R14") (pin "2") (pinfunction "2_2") (pintype "passive"))
      (node (ref "U$12") (pin "14") (pinfunction "OUT_14") (pintype "bidirectional"))
    )
    (net (code "61") (name "Net-(U$13-FB)") (class "Default")
      (node (ref "R5") (pin "1") (pinfunction "1_1") (pintype "passive"))
      (node (ref "R6") (pin "2") (pinfunction "2_2") (pintype "passive"))
      (node (ref "U$13") (pin "13") (pinfunction "FB_13") (pintype "bidirectional"))
    )
    (net (code "62") (name "Net-(U$13-IN0)") (class "Default")
      (node (ref "INA1") (pin "PIN") (pinfunction "PIN_PIN") (pintype "bidirectional"))
      (node (ref "R1") (pin "2") (pinfunction "2_2") (pintype "passive"))
      (node (ref "U$13") (pin "5") (pinfunction "IN0_5") (pintype "bidirectional"))
    )
    (net (code "63") (name "Net-(U$13-IN1)") (class "Default")
      (node (ref "INA2") (pin "PIN") (pinfunction "PIN_PIN") (pintype "bidirectional"))
      (node (ref "R2") (pin "2") (pinfunction "2_2") (pintype "passive"))
      (node (ref "U$13") (pin "7") (pinfunction "IN1_7") (pintype "bidirectional"))
    )
    (net (code "64") (name "Net-(U$13-IN2)") (class "Default")
      (node (ref "INA3") (pin "PIN") (pinfunction "PIN_PIN") (pintype "bidirectional"))
      (node (ref "R3") (pin "2") (pinfunction "2_2") (pintype "passive"))
      (node (ref "U$13") (pin "8") (pinfunction "IN2_8") (pintype "bidirectional"))
    )
    (net (code "65") (name "Net-(U$13-IN3)") (class "Default")
      (node (ref "INA4") (pin "PIN") (pinfunction "PIN_PIN") (pintype "bidirectional"))
      (node (ref "R4") (pin "2") (pinfunction "2_2") (pintype "passive"))
      (node (ref "U$13") (pin "10") (pinfunction "IN3_10") (pintype "bidirectional"))
    )
    (net (code "66") (name "Net-(U$13-OUT)") (class "Default")
      (node (ref "R5") (pin "2") (pinfunction "2_2") (pintype "passive"))
      (node (ref "R7") (pin "2") (pinfunction "2_2") (pintype "passive"))
      (node (ref "U$13") (pin "14") (pinfunction "OUT_14") (pintype "bidirectional"))
    )
    (net (code "67") (name "unconnected-(IC2A-QA-Pad15)") (class "Default")
      (node (ref "IC2") (pin "15") (pinfunction "QA_15") (pintype "tri_state"))
    )
    (net (code "68") (name "unconnected-(IC2A-QB-Pad1)") (class "Default")
      (node (ref "IC2") (pin "1") (pinfunction "QB_1") (pintype "tri_state"))
    )
    (net (code "69") (name "unconnected-(IC2A-QC-Pad2)") (class "Default")
      (node (ref "IC2") (pin "2") (pinfunction "QC_2") (pintype "tri_state"))
    )
    (net (code "70") (name "unconnected-(IC2A-QD-Pad3)") (class "Default")
      (node (ref "IC2") (pin "3") (pinfunction "QD_3") (pintype "tri_state"))
    )
    (net (code "71") (name "unconnected-(IC2A-QH*-Pad9)") (class "Default")
      (node (ref "IC2") (pin "9") (pinfunction "QH*_9") (pintype "tri_state"))
    )
    (net (code "72") (name "unconnected-(INB1-R2-PadP$3)") (class "Default")
      (node (ref "INB1") (pin "P$3") (pinfunction "R2_P$3") (pintype "bidirectional"))
    )
    (net (code "73") (name "unconnected-(INB1-R3-PadP$4)") (class "Default")
      (node (ref "INB1") (pin "P$4") (pinfunction "R3_P$4") (pintype "bidirectional"))
    )
    (net (code "74") (name "unconnected-(INB1-R4-PadP$5)") (class "Default")
      (node (ref "INB1") (pin "P$5") (pinfunction "R4_P$5") (pintype "bidirectional"))
    )
    (net (code "75") (name "unconnected-(J1-LVP-Pad6)") (class "Default")
      (node (ref "J1") (pin "6") (pinfunction "LVP_6") (pintype "bidirectional"))
    )
    (net (code "76") (name "unconnected-(MIDI-Pad2)") (class "Default")
      (node (ref "MIDI") (pin "2") (pinfunction "2_2") (pintype "bidirectional"))
    )
    (net (code "77") (name "unconnected-(MIDI_IN-Pad1)") (class "Default")
      (node (ref "MIDI_IN") (pin "1") (pinfunction "1_1") (pintype "passive"))
    )
    (net (code "78") (name "unconnected-(MIDI_IN-Pad2)") (class "Default")
      (node (ref "MIDI_IN") (pin "2") (pinfunction "2_2") (pintype "passive"))
    )
    (net (code "79") (name "unconnected-(MIDI_IN-Pad3)") (class "Default")
      (node (ref "MIDI_IN") (pin "3") (pinfunction "3_3") (pintype "passive"))
    )
    (net (code "80") (name "unconnected-(U$2-PadNC)") (class "Default")
      (node (ref "U$2") (pin "NC") (pinfunction "NC_NC") (pintype "bidirectional"))
    )
    (net (code "81") (name "unconnected-(U$12-NC1-Pad3)") (class "Default")
      (node (ref "U$12") (pin "3") (pinfunction "NC1_3") (pintype "bidirectional"))
    )
    (net (code "82") (name "unconnected-(U$12-NC2-Pad6)") (class "Default")
      (node (ref "U$12") (pin "6") (pinfunction "NC2_6") (pintype "bidirectional"))
    )
    (net (code "83") (name "unconnected-(U$12-NC3-Pad9)") (class "Default")
      (node (ref "U$12") (pin "9") (pinfunction "NC3_9") (pintype "bidirectional"))
    )
    (net (code "84") (name "unconnected-(U$13-NC1-Pad3)") (class "Default")
      (node (ref "U$13") (pin "3") (pinfunction "NC1_3") (pintype "bidirectional"))
    )
    (net (code "85") (name "unconnected-(U$13-NC2-Pad6)") (class "Default")
      (node (ref "U$13") (pin "6") (pinfunction "NC2_6") (pintype "bidirectional"))
    )
    (net (code "86") (name "unconnected-(U$13-NC3-Pad9)") (class "Default")
      (node (ref "U$13") (pin "9") (pinfunction "NC3_9") (pintype "bidirectional"))
    )
  )
)
